# PAGE12.net
KiCad netlist of a schematic drawn in Altium Designer
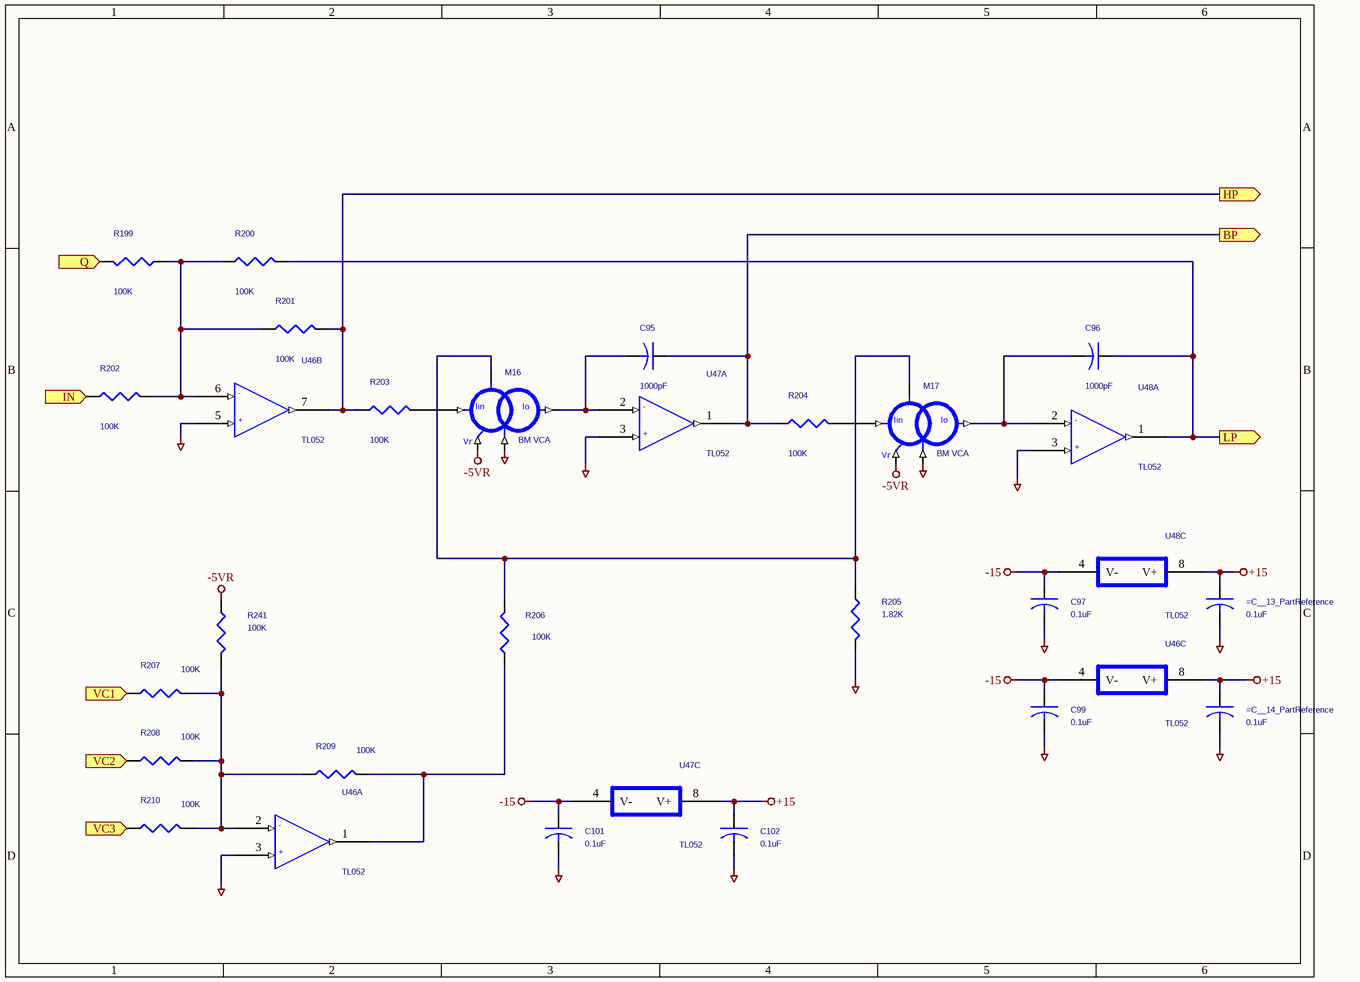
[diagram p0: PAGE12.SchDoc]

(export (version "E")
  (design (tool "Eeschema 10.0.6"))
  (components
    (comp (ref "=C__13_PartReference") (value "0.1uF") (libsource (lib "*") (part "CAP_Dup1")))
    (comp (ref "=C__14_PartReference") (value "0.1uF") (libsource (lib "*") (part "CAP_Dup1")))
    (comp (ref "C95") (value "1000pF") (libsource (lib "*") (part "CAP_Dup1")))
    (comp (ref "C96") (value "1000pF") (libsource (lib "*") (part "CAP_Dup1")))
    (comp (ref "C97") (value "0.1uF") (libsource (lib "*") (part "CAP_Dup1")))
    (comp (ref "C99") (value "0.1uF") (libsource (lib "*") (part "CAP_Dup1")))
    (comp (ref "C101") (value "0.1uF") (libsource (lib "*") (part "CAP_Dup1")))
    (comp (ref "C102") (value "0.1uF") (libsource (lib "*") (part "CAP_Dup1")))
    (comp (ref "M16") (value "BM VCA") (libsource (lib "*") (part "BM VCA")))
    (comp (ref "M17") (value "BM VCA") (libsource (lib "*") (part "BM VCA")))
    (comp (ref "R199") (value "100K") (libsource (lib "*") (part "R_Dup1")))
    (comp (ref "R200") (value "100K") (libsource (lib "*") (part "R_Dup1")))
    (comp (ref "R201") (value "100K") (libsource (lib "*") (part "R_Dup1")))
    (comp (ref "R202") (value "100K") (libsource (lib "*") (part "R_Dup1")))
    (comp (ref "R203") (value "100K") (libsource (lib "*") (part "R_Dup1")))
    (comp (ref "R204") (value "100K") (libsource (lib "*") (part "R_Dup1")))
    (comp (ref "R205") (value "1.82K") (libsource (lib "*") (part "R_Dup1")))
    (comp (ref "R206") (value "100K") (libsource (lib "*") (part "R_Dup1")))
    (comp (ref "R207") (value "100K") (libsource (lib "*") (part "R_Dup1")))
    (comp (ref "R208") (value "100K") (libsource (lib "*") (part "R_Dup1")))
    (comp (ref "R209") (value "100K") (libsource (lib "*") (part "R_Dup1")))
    (comp (ref "R210") (value "100K") (libsource (lib "*") (part "R_Dup1")))
    (comp (ref "R241") (value "100K") (libsource (lib "*") (part "R_Dup1")))
    (comp (ref "U46") (value "TL052") (footprint "DIP8") (libsource (lib "*") (part "GEN DUAL OPAMP-H")))
    (comp (ref "U47") (value "TL052") (footprint "DIP8") (libsource (lib "*") (part "GEN DUAL OPAMP-H")))
    (comp (ref "U48") (value "TL052") (footprint "DIP8") (libsource (lib "*") (part "GEN DUAL OPAMP-H")))
  )
  (nets
    (net (code "1") (name "+15") (class "Default")
      (node (ref "=C__13_PartReference") (pin "1") (pinfunction "1_1") (pintype "passive"))
      (node (ref "=C__14_PartReference") (pin "1") (pinfunction "1_1") (pintype "passive"))
      (node (ref "C102") (pin "1") (pinfunction "1_1") (pintype "passive"))
      (node (ref "U46") (pin "8") (pinfunction "V+_8") (pintype "passive"))
      (node (ref "U47") (pin "8") (pinfunction "V+_8") (pintype "passive"))
      (node (ref "U48") (pin "8") (pinfunction "V+_8") (pintype "passive"))
    )
    (net (code "2") (name "-5VR") (class "Default")
      (node (ref "M16") (pin "-VR") (pinfunction "-VR_-VR") (pintype "input"))
      (node (ref "M17") (pin "-VR") (pinfunction "-VR_-VR") (pintype "input"))
      (node (ref "R241") (pin "1") (pinfunction "1_1") (pintype "passive"))
    )
    (net (code "3") (name "-15") (class "Default")
      (node (ref "C101") (pin "1") (pinfunction "1_1") (pintype "passive"))
      (node (ref "C97") (pin "1") (pinfunction "1_1") (pintype "passive"))
      (node (ref "C99") (pin "1") (pinfunction "1_1") (pintype "passive"))
      (node (ref "U46") (pin "4") (pinfunction "V-_4") (pintype "passive"))
      (node (ref "U47") (pin "4") (pinfunction "V-_4") (pintype "passive"))
      (node (ref "U48") (pin "4") (pinfunction "V-_4") (pintype "passive"))
    )
    (net (code "4") (name "/BP") (class "Default")
      (node (ref "C95") (pin "1") (pinfunction "1_1") (pintype "passive"))
      (node (ref "R204") (pin "1") (pinfunction "1_1") (pintype "passive"))
      (node (ref "U47") (pin "1") (pinfunction "OUT_1") (pintype "output"))
    )
    (net (code "5") (name "/HP") (class "Default")
      (node (ref "R201") (pin "2") (pinfunction "2_2") (pintype "passive"))
      (node (ref "R203") (pin "1") (pinfunction "1_1") (pintype "passive"))
      (node (ref "U46") (pin "7") (pinfunction "OUT_7") (pintype "output"))
    )
    (net (code "6") (name "/IN") (class "Default")
      (node (ref "R202") (pin "1") (pinfunction "1_1") (pintype "passive"))
    )
    (net (code "7") (name "/LP") (class "Default")
      (node (ref "C96") (pin "1") (pinfunction "1_1") (pintype "passive"))
      (node (ref "R200") (pin "2") (pinfunction "2_2") (pintype "passive"))
      (node (ref "U48") (pin "1") (pinfunction "OUT_1") (pintype "output"))
    )
    (net (code "8") (name "/Q") (class "Default")
      (node (ref "R199") (pin "2") (pinfunction "2_2") (pintype "passive"))
    )
    (net (code "9") (name "/VC1") (class "Default")
      (node (ref "R207") (pin "1") (pinfunction "1_1") (pintype "passive"))
    )
    (net (code "10") (name "/VC2") (class "Default")
      (node (ref "R208") (pin "1") (pinfunction "1_1") (pintype "passive"))
    )
    (net (code "11") (name "/VC3") (class "Default")
      (node (ref "R210") (pin "1") (pinfunction "1_1") (pintype "passive"))
    )
    (net (code "12") (name "AGND") (class "Default")
      (node (ref "=C__13_PartReference") (pin "2") (pinfunction "2_2") (pintype "passive"))
      (node (ref "=C__14_PartReference") (pin "2") (pinfunction "2_2") (pintype "passive"))
      (node (ref "C101") (pin "2") (pinfunction "2_2") (pintype "passive"))
      (node (ref "C102") (pin "2") (pinfunction "2_2") (pintype "passive"))
      (node (ref "C97") (pin "2") (pinfunction "2_2") (pintype "passive"))
      (node (ref "C99") (pin "2") (pinfunction "2_2") (pintype "passive"))
      (node (ref "M16") (pin "CVP") (pinfunction "CVP_CVP") (pintype "input"))
      (node (ref "M17") (pin "CVP") (pinfunction "CVP_CVP") (pintype "input"))
      (node (ref "R205") (pin "2") (pinfunction "2_2") (pintype "passive"))
      (node (ref "U46") (pin "3") (pinfunction "+_3") (pintype "input"))
      (node (ref "U46") (pin "5") (pinfunction "+_5") (pintype "input"))
      (node (ref "U47") (pin "3") (pinfunction "+_3") (pintype "input"))
      (node (ref "U48") (pin "3") (pinfunction "+_3") (pintype "input"))
    )
    (net (code "13") (name "Net-(M16-PadCVN)") (class "Default")
      (node (ref "M16") (pin "CVN") (pinfunction "CVN_CVN") (pintype "passive"))
      (node (ref "M17") (pin "CVN") (pinfunction "CVN_CVN") (pintype "passive"))
      (node (ref "R205") (pin "1") (pinfunction "1_1") (pintype "passive"))
      (node (ref "R206") (pin "2") (pinfunction "2_2") (pintype "passive"))
    )
    (net (code "14") (name "Net-(M16-PadIin)") (class "Default")
      (node (ref "M16") (pin "Iin") (pinfunction "Iin_Iin") (pintype "input"))
      (node (ref "R203") (pin "2") (pinfunction "2_2") (pintype "passive"))
    )
    (net (code "15") (name "Net-(M17-PadIin)") (class "Default")
      (node (ref "M17") (pin "Iin") (pinfunction "Iin_Iin") (pintype "input"))
      (node (ref "R204") (pin "2") (pinfunction "2_2") (pintype "passive"))
    )
    (net (code "16") (name "Net-(U46A--)") (class "Default")
      (node (ref "R207") (pin "2") (pinfunction "2_2") (pintype "passive"))
      (node (ref "R208") (pin "2") (pinfunction "2_2") (pintype "passive"))
      (node (ref "R209") (pin "1") (pinfunction "1_1") (pintype "passive"))
      (node (ref "R210") (pin "2") (pinfunction "2_2") (pintype "passive"))
      (node (ref "R241") (pin "2") (pinfunction "2_2") (pintype "passive"))
      (node (ref "U46") (pin "2") (pinfunction "-_2") (pintype "input"))
    )
    (net (code "17") (name "Net-(U46A-OUT)") (class "Default")
      (node (ref "R206") (pin "1") (pinfunction "1_1") (pintype "passive"))
      (node (ref "R209") (pin "2") (pinfunction "2_2") (pintype "passive"))
      (node (ref "U46") (pin "1") (pinfunction "OUT_1") (pintype "output"))
    )
    (net (code "18") (name "Net-(U46B--)") (class "Default")
      (node (ref "R199") (pin "1") (pinfunction "1_1") (pintype "passive"))
      (node (ref "R200") (pin "1") (pinfunction "1_1") (pintype "passive"))
      (node (ref "R201") (pin "1") (pinfunction "1_1") (pintype "passive"))
      (node (ref "R202") (pin "2") (pinfunction "2_2") (pintype "passive"))
      (node (ref "U46") (pin "6") (pinfunction "-_6") (pintype "input"))
    )
    (net (code "19") (name "Net-(U47A--)") (class "Default")
      (node (ref "C95") (pin "2") (pinfunction "2_2") (pintype "passive"))
      (node (ref "M16") (pin "Io") (pinfunction "Io_Io") (pintype "output"))
      (node (ref "U47") (pin "2") (pinfunction "-_2") (pintype "input"))
    )
    (net (code "20") (name "Net-(U48A--)") (class "Default")
      (node (ref "C96") (pin "2") (pinfunction "2_2") (pintype "passive"))
      (node (ref "M17") (pin "Io") (pinfunction "Io_Io") (pintype "output"))
      (node (ref "U48") (pin "2") (pinfunction "-_2") (pintype "input"))
    )
  )
)
